# rectificador.net
KiCad netlist of a schematic drawn in EAGLE
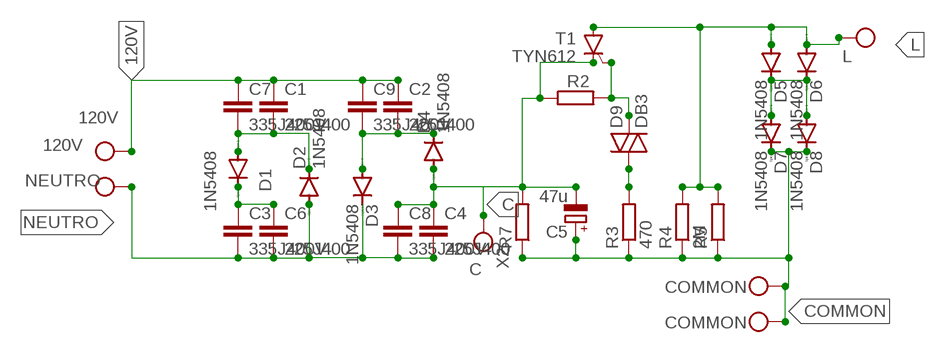
[diagram p0: schematic, sheet 1]

(export (version "E")
  (design (tool "Eeschema 10.0.6"))
  (components
    (comp (ref "C1")
      (value "225J400")
      (footprint "eagle-import:C15B9")
      (libsource (lib "eagle-import") (part "C15/9"))
    )
    (comp (ref "C2")
      (value "225J400")
      (footprint "eagle-import:C15B9")
      (libsource (lib "eagle-import") (part "C15/9"))
    )
    (comp (ref "C3")
      (value "335J400V")
      (footprint "eagle-import:C15B9")
      (libsource (lib "eagle-import") (part "C15/9"))
    )
    (comp (ref "C4")
      (value "225J400")
      (footprint "eagle-import:C15B9")
      (libsource (lib "eagle-import") (part "C15/9"))
    )
    (comp (ref "C5")
      (value "47u")
      (footprint "eagle-import:E2-5")
      (fields (field (name "MF") "PEPPERL+FUCHS") (field (name "MPN") "V3-WM-E2-5M-PUR"))
      (libsource (lib "eagle-import") (part "CPOL-EUE2-5"))
    )
    (comp (ref "C6")
      (value "225J400")
      (footprint "eagle-import:C15B9")
      (fields (field (name "SPICEPREFIX") "C"))
      (libsource (lib "eagle-import") (part "C15/9"))
    )
    (comp (ref "C7")
      (value "335J400V")
      (footprint "eagle-import:C15B9")
      (libsource (lib "eagle-import") (part "C15/9"))
    )
    (comp (ref "C8")
      (value "335J400V")
      (footprint "eagle-import:C15B9")
      (libsource (lib "eagle-import") (part "C15/9"))
    )
    (comp (ref "C9")
      (value "335J400V")
      (footprint "eagle-import:C15B9")
      (libsource (lib "eagle-import") (part "C15/9"))
    )
    (comp (ref "D1")
      (value "1N5408")
      (footprint "eagle-import:DO201-15")
      (libsource (lib "eagle-import") (part "1N5400"))
    )
    (comp (ref "D2")
      (value "1N5408")
      (footprint "eagle-import:DO201-15")
      (libsource (lib "eagle-import") (part "1N5400"))
    )
    (comp (ref "D3")
      (value "1N5408")
      (footprint "eagle-import:DO201-15")
      (libsource (lib "eagle-import") (part "1N5400"))
    )
    (comp (ref "D4")
      (value "1N5408")
      (footprint "eagle-import:DO201-15")
      (libsource (lib "eagle-import") (part "1N5400"))
    )
    (comp (ref "D5")
      (value "1N5408")
      (footprint "eagle-import:DO201-15")
      (libsource (lib "eagle-import") (part "1N5400"))
    )
    (comp (ref "D6")
      (value "1N5408")
      (footprint "eagle-import:DO201-15")
      (libsource (lib "eagle-import") (part "1N5400"))
    )
    (comp (ref "D7")
      (value "1N5408")
      (footprint "eagle-import:DO201-15")
      (libsource (lib "eagle-import") (part "1N5400"))
    )
    (comp (ref "D8")
      (value "1N5408")
      (footprint "eagle-import:DO201-15")
      (libsource (lib "eagle-import") (part "1N5400"))
    )
    (comp (ref "D9")
      (value "DB3")
      (footprint "eagle-import:DO35-10")
      (libsource (lib "eagle-import") (part "DIAC-DO35-10"))
    )
    (comp (ref "R2")
      (value "R-EU_0207/10")
      (footprint "eagle-import:0207_10")
      (libsource (lib "eagle-import") (part "R-EU_0207/10"))
    )
    (comp (ref "R3")
      (value "470")
      (footprint "eagle-import:0207_10")
      (libsource (lib "eagle-import") (part "R-EU_0207/10"))
    )
    (comp (ref "R4")
      (value "2M")
      (footprint "eagle-import:0207_10")
      (libsource (lib "eagle-import") (part "R-EU_0207/10"))
    )
    (comp (ref "R5")
      (value "R-EU_0207/10")
      (footprint "eagle-import:0207_10")
      (libsource (lib "eagle-import") (part "R-EU_0207/10"))
    )
    (comp (ref "R7")
      (value "R-EU_0207/10")
      (footprint "eagle-import:0207_10")
      (libsource (lib "eagle-import") (part "R-EU_0207/10"))
    )
    (comp (ref "T1")
      (value "TYN612")
      (footprint "eagle-import:TO220CS")
      (libsource (lib "eagle-import") (part "TIC126"))
    )
    (comp (ref "VIN")
      (value "120V")
      (footprint "eagle-import:W237-102")
      (fields (field (name "MPN") "237-102") (field (name "MF") "WAGO"))
      (libsource (lib "eagle-import") (part "W237-102"))
    )
    (comp (ref "X2")
      (value "X2")
      (footprint "eagle-import:W237-4")
      (libsource (lib "eagle-import") (part "W237-4"))
    )
  )
  (nets
    (net (code "1") (name "120V") (class "Default")
      (node (ref "C1") (pin "1") (pinfunction "1_1") (pintype "passive"))
      (node (ref "C2") (pin "1") (pinfunction "1_1") (pintype "passive"))
      (node (ref "C7") (pin "1") (pinfunction "1_1") (pintype "passive"))
      (node (ref "C9") (pin "1") (pinfunction "1_1") (pintype "passive"))
      (node (ref "VIN") (pin "2") (pinfunction "KL_2") (pintype "passive"))
    )
    (net (code "2") (name "C") (class "Default")
      (node (ref "C4") (pin "1") (pinfunction "1_1") (pintype "passive"))
      (node (ref "C5") (pin "-") (pinfunction "-_-") (pintype "passive"))
      (node (ref "C8") (pin "1") (pinfunction "1_1") (pintype "passive"))
      (node (ref "D4") (pin "A") (pinfunction "A_A") (pintype "passive"))
      (node (ref "R2") (pin "1") (pinfunction "1_1") (pintype "passive"))
      (node (ref "R7") (pin "2") (pinfunction "2_2") (pintype "passive"))
      (node (ref "T1") (pin "C") (pinfunction "C_C") (pintype "passive"))
      (node (ref "X2") (pin "4") (pinfunction "KL_4") (pintype "passive"))
    )
    (net (code "3") (name "COMMON") (class "Default")
      (node (ref "C5") (pin "+") (pinfunction "+_+") (pintype "passive"))
      (node (ref "D7") (pin "C") (pinfunction "C_C") (pintype "passive"))
      (node (ref "D8") (pin "C") (pinfunction "C_C") (pintype "passive"))
      (node (ref "R3") (pin "1") (pinfunction "1_1") (pintype "passive"))
      (node (ref "R4") (pin "1") (pinfunction "1_1") (pintype "passive"))
      (node (ref "R5") (pin "1") (pinfunction "1_1") (pintype "passive"))
      (node (ref "R7") (pin "1") (pinfunction "1_1") (pintype "passive"))
      (node (ref "X2") (pin "2") (pinfunction "KL_2") (pintype "passive"))
      (node (ref "X2") (pin "3") (pinfunction "KL_3") (pintype "passive"))
    )
    (net (code "4") (name "L") (class "Default")
      (node (ref "D5") (pin "A") (pinfunction "A_A") (pintype "passive"))
      (node (ref "D6") (pin "A") (pinfunction "A_A") (pintype "passive"))
      (node (ref "R4") (pin "2") (pinfunction "2_2") (pintype "passive"))
      (node (ref "R5") (pin "2") (pinfunction "2_2") (pintype "passive"))
      (node (ref "T1") (pin "A") (pinfunction "A_A") (pintype "passive"))
      (node (ref "X2") (pin "1") (pinfunction "KL_1") (pintype "passive"))
    )
    (net (code "5") (name "NEUTRO") (class "Default")
      (node (ref "C3") (pin "2") (pinfunction "2_2") (pintype "passive"))
      (node (ref "C4") (pin "2") (pinfunction "2_2") (pintype "passive"))
      (node (ref "C6") (pin "2") (pinfunction "2_2") (pintype "passive"))
      (node (ref "C8") (pin "2") (pinfunction "2_2") (pintype "passive"))
      (node (ref "D2") (pin "A") (pinfunction "A_A") (pintype "passive"))
      (node (ref "D3") (pin "C") (pinfunction "C_C") (pintype "passive"))
      (node (ref "VIN") (pin "1") (pinfunction "KL_1") (pintype "passive"))
    )
    (net (code "6") (name "Net-(C1-Pad2)") (class "Default")
      (node (ref "C1") (pin "2") (pinfunction "2_2") (pintype "passive"))
      (node (ref "C7") (pin "2") (pinfunction "2_2") (pintype "passive"))
      (node (ref "D1") (pin "A") (pinfunction "A_A") (pintype "passive"))
      (node (ref "D2") (pin "C") (pinfunction "C_C") (pintype "passive"))
    )
    (net (code "7") (name "Net-(C2-Pad2)") (class "Default")
      (node (ref "C2") (pin "2") (pinfunction "2_2") (pintype "passive"))
      (node (ref "C9") (pin "2") (pinfunction "2_2") (pintype "passive"))
      (node (ref "D3") (pin "A") (pinfunction "A_A") (pintype "passive"))
      (node (ref "D4") (pin "C") (pinfunction "C_C") (pintype "passive"))
    )
    (net (code "8") (name "Net-(C3-Pad1)") (class "Default")
      (node (ref "C3") (pin "1") (pinfunction "1_1") (pintype "passive"))
      (node (ref "C6") (pin "1") (pinfunction "1_1") (pintype "passive"))
      (node (ref "D1") (pin "C") (pinfunction "C_C") (pintype "passive"))
    )
    (net (code "9") (name "Net-(D5-PadC)") (class "Default")
      (node (ref "D5") (pin "C") (pinfunction "C_C") (pintype "passive"))
      (node (ref "D6") (pin "C") (pinfunction "C_C") (pintype "passive"))
      (node (ref "D7") (pin "A") (pinfunction "A_A") (pintype "passive"))
      (node (ref "D8") (pin "A") (pinfunction "A_A") (pintype "passive"))
    )
    (net (code "10") (name "Net-(D9-1)") (class "Default")
      (node (ref "D9") (pin "A") (pinfunction "1_A") (pintype "passive"))
      (node (ref "R3") (pin "2") (pinfunction "2_2") (pintype "passive"))
    )
    (net (code "11") (name "Net-(D9-2)") (class "Default")
      (node (ref "D9") (pin "C") (pinfunction "2_C") (pintype "passive"))
      (node (ref "R2") (pin "2") (pinfunction "2_2") (pintype "passive"))
      (node (ref "T1") (pin "G") (pinfunction "G_G") (pintype "passive"))
    )
  )
)
